# Interface.net
KiCad netlist of a schematic drawn in Altium Designer
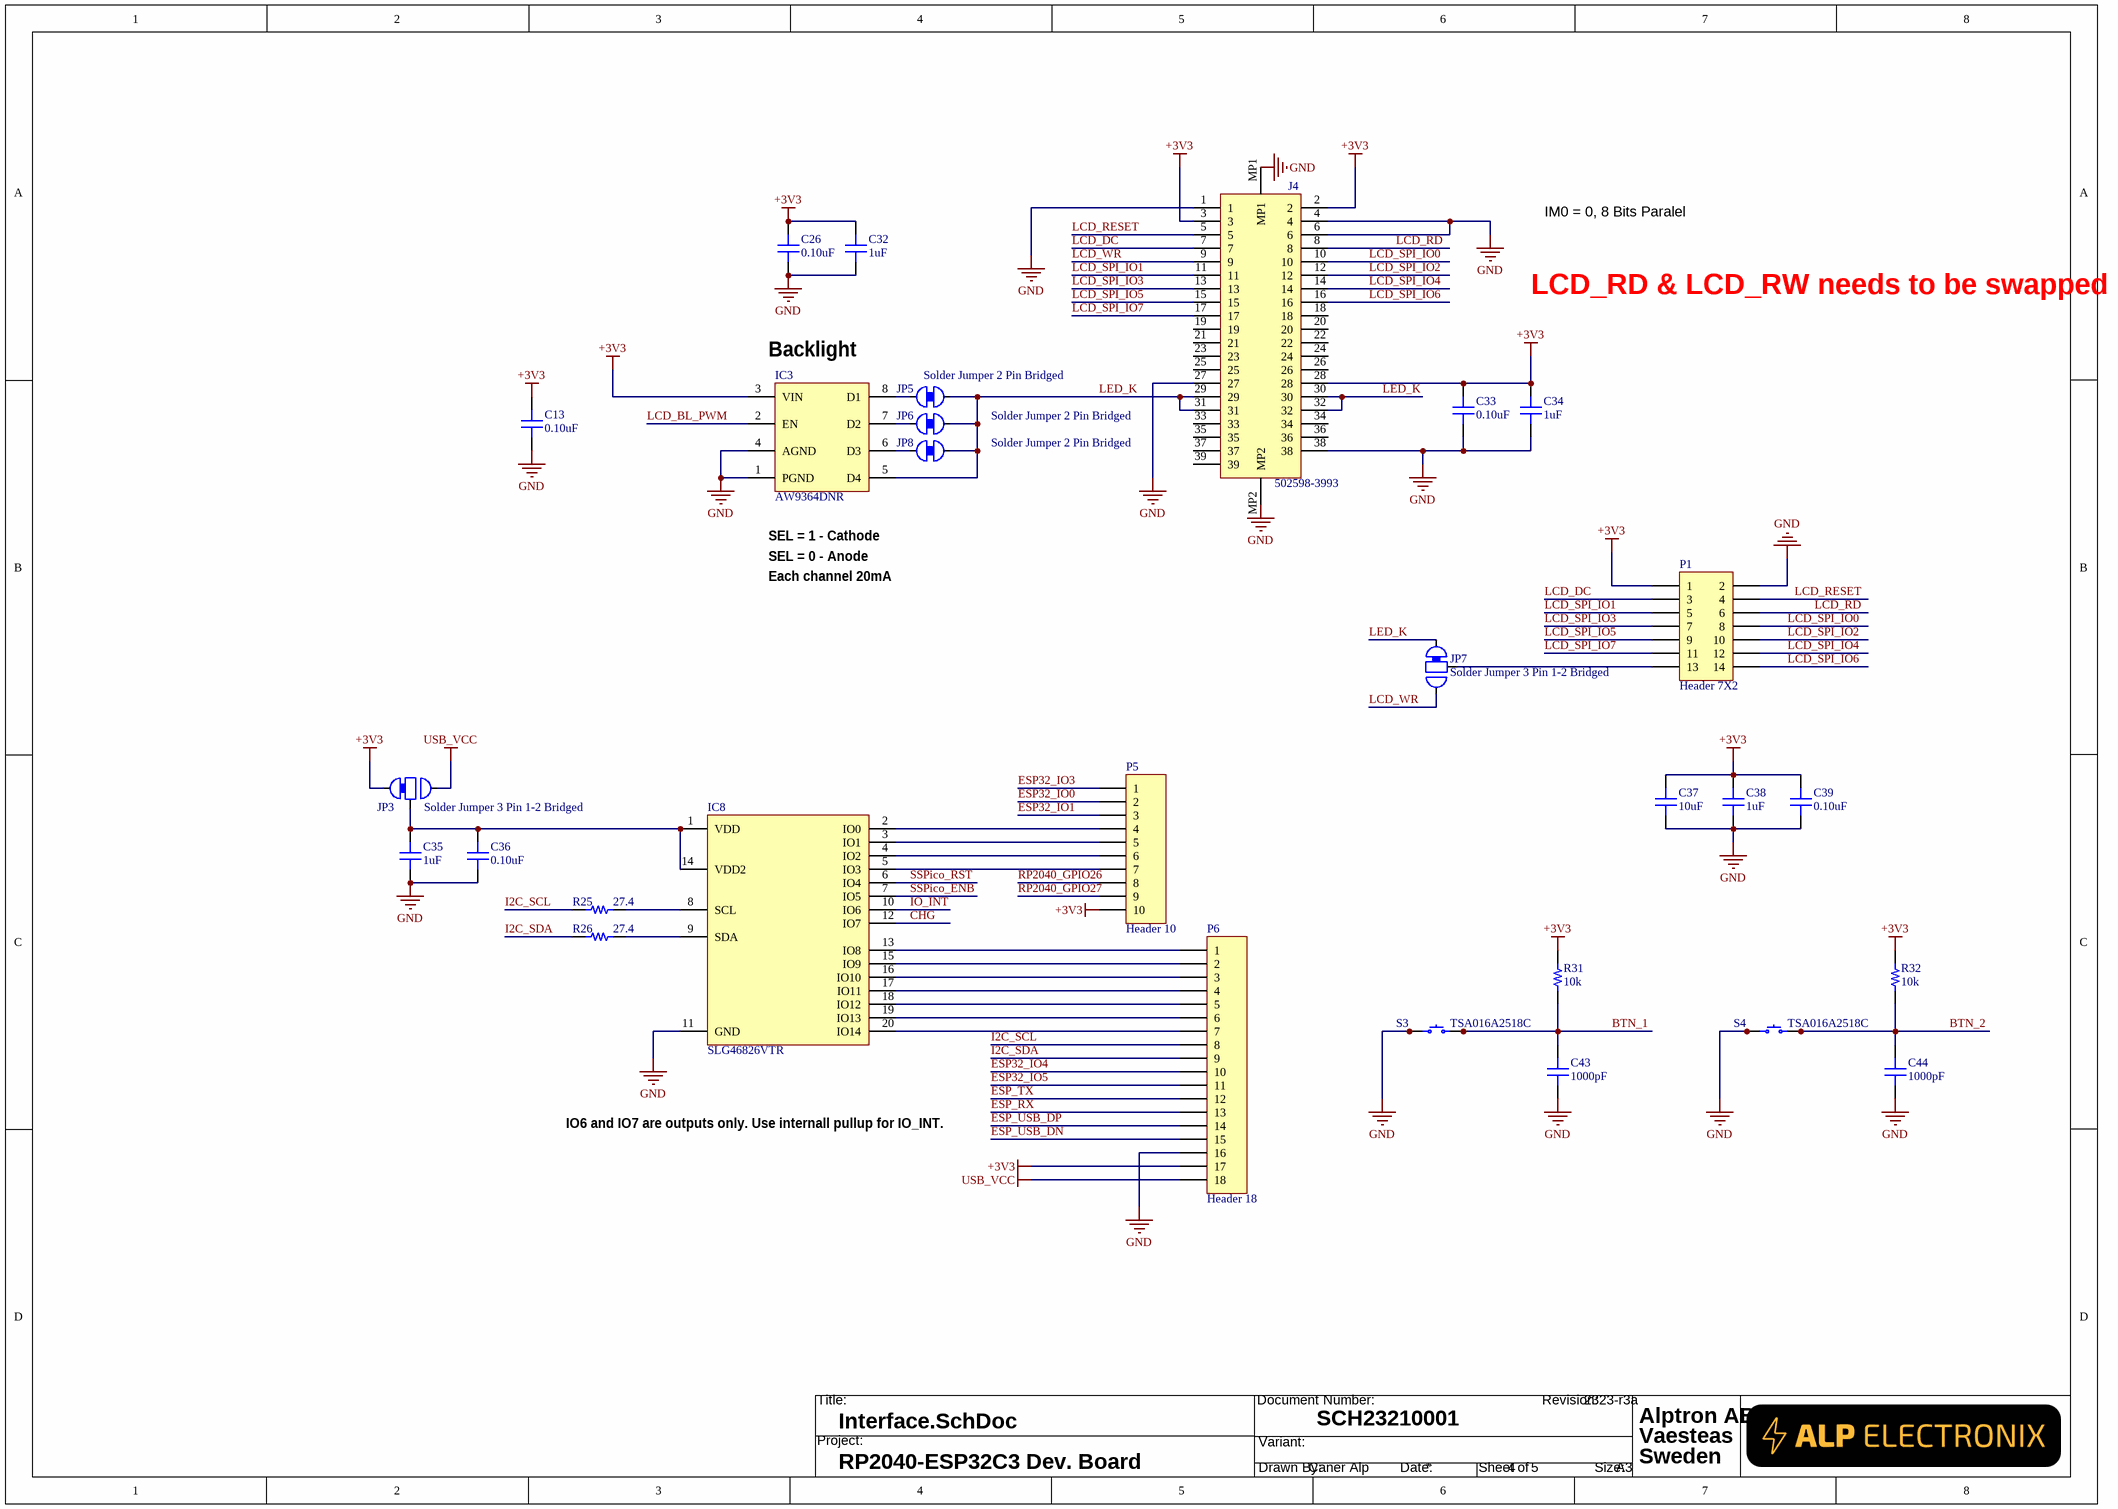
[diagram p0: Interface.SchDoc]

(export (version "E")
  (design (tool "Eeschema 10.0.6"))
  (components
    (comp (ref "C13")
      (value "0.10uF")
      (footprint "CAP 0402/1005")
      (description "CAP CER 0.1UF 10V X5R 0402")
      (fields (field (name "PART NUMBER") "LMK105BJ104KV-F") (field (name "MANUFACTURER") "Taiyo Yuden"))
      (libsource (lib "Celestial Library Database") (part "Capacitor"))
    )
    (comp (ref "C26")
      (value "0.10uF")
      (footprint "CAP 0402/1005")
      (description "CAP CER 0.1UF 10V X5R 0402")
      (fields (field (name "PART NUMBER") "LMK105BJ104KV-F") (field (name "MANUFACTURER") "Taiyo Yuden"))
      (libsource (lib "Celestial Library Database") (part "Capacitor"))
    )
    (comp (ref "C32")
      (value "1uF")
      (footprint "CAP 0402/1005")
      (description "CAP CER 1UF 6.3V X7R 0402")
      (fields
        (field (name "PART NUMBER") "GRM155R70J105KA12D")
        (field (name "MANUFACTURER") "Murata Electronics North America")
      )
      (libsource (lib "Celestial Library Database") (part "Capacitor"))
    )
    (comp (ref "C33")
      (value "0.10uF")
      (footprint "CAP 0402/1005")
      (description "CAP CER 0.1UF 10V X5R 0402")
      (fields (field (name "PART NUMBER") "LMK105BJ104KV-F") (field (name "MANUFACTURER") "Taiyo Yuden"))
      (libsource (lib "Celestial Library Database") (part "Capacitor"))
    )
    (comp (ref "C34")
      (value "1uF")
      (footprint "CAP 0402/1005")
      (description "CAP CER 1UF 6.3V X7R 0402")
      (fields
        (field (name "PART NUMBER") "GRM155R70J105KA12D")
        (field (name "MANUFACTURER") "Murata Electronics North America")
      )
      (libsource (lib "Celestial Library Database") (part "Capacitor"))
    )
    (comp (ref "C35")
      (value "1uF")
      (footprint "CAP 0402/1005")
      (description "CAP CER 1UF 6.3V X7R 0402")
      (fields
        (field (name "PART NUMBER") "GRM155R70J105KA12D")
        (field (name "MANUFACTURER") "Murata Electronics North America")
      )
      (libsource (lib "Celestial Library Database") (part "Capacitor"))
    )
    (comp (ref "C36")
      (value "0.10uF")
      (footprint "CAP 0402/1005")
      (description "CAP CER 0.1UF 10V X5R 0402")
      (fields (field (name "PART NUMBER") "LMK105BJ104KV-F") (field (name "MANUFACTURER") "Taiyo Yuden"))
      (libsource (lib "Celestial Library Database") (part "Capacitor"))
    )
    (comp (ref "C37")
      (value "10uF")
      (footprint "CAP 0603/1608")
      (description "CAP CER 10UF 6.3V X5R 0603")
      (fields
        (field (name "PART NUMBER") "GRM188R60J106ME47D")
        (field (name "MANUFACTURER") "Murata Electronics North America")
      )
      (libsource (lib "Celestial Library Database") (part "Capacitor"))
    )
    (comp (ref "C38")
      (value "1uF")
      (footprint "CAP 0402/1005")
      (description "CAP CER 1UF 6.3V X7R 0402")
      (fields
        (field (name "PART NUMBER") "GRM155R70J105KA12D")
        (field (name "MANUFACTURER") "Murata Electronics North America")
      )
      (libsource (lib "Celestial Library Database") (part "Capacitor"))
    )
    (comp (ref "C39")
      (value "0.10uF")
      (footprint "CAP 0402/1005")
      (description "CAP CER 0.1UF 10V X5R 0402")
      (fields (field (name "PART NUMBER") "LMK105BJ104KV-F") (field (name "MANUFACTURER") "Taiyo Yuden"))
      (libsource (lib "Celestial Library Database") (part "Capacitor"))
    )
    (comp (ref "C43")
      (value "1000pF")
      (footprint "CAP 0402/1005")
      (description "CAP CER 1000PF 50V C0G 0402")
      (fields
        (field (name "PART NUMBER") "C1005C0G1H102J050BA")
        (field (name "MANUFACTURER") "TDK Corporation")
      )
      (libsource (lib "Celestial Library Database") (part "Capacitor"))
    )
    (comp (ref "C44")
      (value "1000pF")
      (footprint "CAP 0402/1005")
      (description "CAP CER 1000PF 50V C0G 0402")
      (fields
        (field (name "PART NUMBER") "C1005C0G1H102J050BA")
        (field (name "MANUFACTURER") "TDK Corporation")
      )
      (libsource (lib "Celestial Library Database") (part "Capacitor"))
    )
    (comp (ref "IC3")
      (value "AW9364DNR")
      (footprint "RP2040_ESP32-C3 Dev Board PCB Lib:MAXIM TDFN-8 2x2MM")
      (description "-40℃~+85℃ DFN-8(2x2) LED Drivers ROHS")
      (libsource (lib "RP2040_ESP32-C3 Dev Board SCH Lib") (part "AW9364DNR"))
    )
    (comp (ref "IC8")
      (value "SLG46826VTR")
      (footprint "RP2040_ESP32-C3 Dev Board PCB Lib:SLG46826VTR")
      (fields
        (field (name "MOUSER PART NUMBER") "724-SLG46826VTR")
        (field (name "MANUFACTURER") "Renesas")
        (field (name "MANUFACTURER PART NUMBER") "SLG46826V")
      )
      (libsource (lib "RP2040_ESP32-C3 Dev Board SCH Lib") (part "SLG46826VTR"))
    )
    (comp (ref "J4")
      (value "502598-3993")
      (footprint "RP2040_ESP32-C3 Dev Board PCB Lib:5025983993")
      (description "Connector")
      (fields (field (name "MOUSER PART NUMBER") "538-502598-3993"))
      (libsource (lib "RP2040_ESP32-C3 Dev Board SCH Lib") (part "502598-3993"))
    )
    (comp (ref "JP3")
      (value "Solder Jumper 3 Pin 1-2 Bridged")
      (footprint "Jumper:SolderJumper-3_P1.3mm_Bridged12_RoundedPad1.0x1.5mm")
      (libsource (lib "Jumper") (part "SolderJumper_3_Bridged12"))
    )
    (comp (ref "JP5")
      (value "Solder Jumper 2 Pin Bridged")
      (footprint "Jumper:SolderJumper-2_P1.3mm_Bridged_RoundedPad1.0x1.5mm")
      (libsource (lib "Jumper") (part "SolderJumper_2_Bridged"))
    )
    (comp (ref "JP6")
      (value "Solder Jumper 2 Pin Bridged")
      (footprint "Jumper:SolderJumper-2_P1.3mm_Bridged_RoundedPad1.0x1.5mm")
      (libsource (lib "Jumper") (part "SolderJumper_2_Bridged"))
    )
    (comp (ref "JP7")
      (value "Solder Jumper 3 Pin 1-2 Bridged")
      (footprint "Jumper:SolderJumper-3_P1.3mm_Bridged12_RoundedPad1.0x1.5mm")
      (libsource (lib "") (part "SolderJumper_3_Bridged12_1"))
    )
    (comp (ref "JP8")
      (value "Solder Jumper 2 Pin Bridged")
      (footprint "Jumper:SolderJumper-2_P1.3mm_Bridged_RoundedPad1.0x1.5mm")
      (libsource (lib "Jumper") (part "SolderJumper_2_Bridged"))
    )
    (comp (ref "P1")
      (value "Header 7X2")
      (footprint "HDR2X7")
      (description "Header, 7-Pin, Dual row")
      (fields (field (name "PUBLISHER") "Altium Limited"))
      (libsource (lib "Miscellaneous Connectors") (part "Header 7X2"))
    )
    (comp (ref "P5")
      (value "Header 10")
      (footprint "3D FootPrint_Backup:Female Header 2.54mm - 10 Pin")
      (description "Header, 10-Pin")
      (fields (field (name "PUBLISHER") "Altium Limited"))
      (libsource (lib "Miscellaneous Connectors") (part "Header 10"))
    )
    (comp (ref "P6")
      (value "Header 18")
      (footprint "3D FootPrint_Backup:Female Header 2.54mm - 18 Pin")
      (description "Header, 18-Pin")
      (fields (field (name "PUBLISHER") "Altium Limited"))
      (libsource (lib "Miscellaneous Connectors") (part "Header 18"))
    )
    (comp (ref "R25")
      (value "27.4")
      (footprint "RES 0402/1005")
      (description "RES SMD 27.4 OHM 1% 1/10W 0402")
      (fields
        (field (name "PART NUMBER") "ERJ-2RKF27R4X")
        (field (name "MANUFACTURER") "Panasonic Electronic Components")
      )
      (libsource (lib "Celestial Library Database") (part "Resistor"))
    )
    (comp (ref "R26")
      (value "27.4")
      (footprint "RES 0402/1005")
      (description "RES SMD 27.4 OHM 1% 1/10W 0402")
      (fields
        (field (name "PART NUMBER") "ERJ-2RKF27R4X")
        (field (name "MANUFACTURER") "Panasonic Electronic Components")
      )
      (libsource (lib "Celestial Library Database") (part "Resistor"))
    )
    (comp (ref "R31")
      (value "10k")
      (footprint "RES 0402/1005")
      (description "RES SMD 10K OHM 5% 1/16W 0402")
      (fields (field (name "PART NUMBER") "RC0402JR-0710KL") (field (name "MANUFACTURER") "Yageo"))
      (libsource (lib "Celestial Library Database") (part "Resistor"))
    )
    (comp (ref "R32")
      (value "10k")
      (footprint "RES 0402/1005")
      (description "RES SMD 10K OHM 5% 1/16W 0402")
      (fields (field (name "PART NUMBER") "RC0402JR-0710KL") (field (name "MANUFACTURER") "Yageo"))
      (libsource (lib "Celestial Library Database") (part "Resistor"))
    )
    (comp (ref "S3")
      (value "TSA016A2518C")
      (footprint "RP2040_ESP32-C3 Dev Board PCB Lib:TSA016A2518C")
      (description "SWITCH TACTILE SPST-NO 0.05A 16V")
      (fields (field (name "MANUFACTURER") "C&K"))
      (libsource (lib "Celestial Altium Library - altium_library") (part "SPST-NO 4 PIN"))
    )
    (comp (ref "S4")
      (value "TSA016A2518C")
      (footprint "RP2040_ESP32-C3 Dev Board PCB Lib:TSA016A2518C")
      (description "SWITCH TACTILE SPST-NO 0.05A 16V")
      (fields (field (name "MANUFACTURER") "C&K"))
      (libsource (lib "Celestial Altium Library - altium_library") (part "SPST-NO 4 PIN"))
    )
  )
  (nets
    (net (code "1") (name "+3V3") (class "Default")
      (node (ref "C13") (pin "2") (pinfunction "2_2") (pintype "passive"))
      (node (ref "C26") (pin "2") (pinfunction "2_2") (pintype "passive"))
      (node (ref "C32") (pin "2") (pinfunction "2_2") (pintype "passive"))
      (node (ref "C33") (pin "2") (pinfunction "2_2") (pintype "passive"))
      (node (ref "C34") (pin "2") (pinfunction "2_2") (pintype "passive"))
      (node (ref "C37") (pin "2") (pinfunction "2_2") (pintype "passive"))
      (node (ref "C38") (pin "2") (pinfunction "2_2") (pintype "passive"))
      (node (ref "C39") (pin "2") (pinfunction "2_2") (pintype "passive"))
      (node (ref "IC3") (pin "3") (pinfunction "VIN_3") (pintype "passive"))
      (node (ref "J4") (pin "2") (pinfunction "2_2") (pintype "passive"))
      (node (ref "J4") (pin "28") (pinfunction "28_28") (pintype "passive"))
      (node (ref "J4") (pin "3") (pinfunction "3_3") (pintype "passive"))
      (node (ref "JP3") (pin "1") (pinfunction "A_1") (pintype "passive"))
      (node (ref "P1") (pin "1") (pinfunction "1_1") (pintype "passive"))
      (node (ref "P5") (pin "10") (pinfunction "10_10") (pintype "passive"))
      (node (ref "P6") (pin "17") (pinfunction "17_17") (pintype "passive"))
      (node (ref "R31") (pin "2") (pinfunction "2_2") (pintype "passive"))
      (node (ref "R32") (pin "2") (pinfunction "2_2") (pintype "passive"))
    )
    (net (code "2") (name "/BTN_1") (class "Default")
      (node (ref "C43") (pin "2") (pinfunction "2_2") (pintype "passive"))
      (node (ref "R31") (pin "1") (pinfunction "1_1") (pintype "passive"))
      (node (ref "S3") (pin "3") (pinfunction "3_3") (pintype "passive"))
      (node (ref "S3") (pin "4") (pinfunction "4_4") (pintype "passive"))
    )
    (net (code "3") (name "/BTN_2") (class "Default")
      (node (ref "C44") (pin "2") (pinfunction "2_2") (pintype "passive"))
      (node (ref "R32") (pin "1") (pinfunction "1_1") (pintype "passive"))
      (node (ref "S4") (pin "3") (pinfunction "3_3") (pintype "passive"))
      (node (ref "S4") (pin "4") (pinfunction "4_4") (pintype "passive"))
    )
    (net (code "4") (name "/CHG") (class "Default")
      (node (ref "IC8") (pin "12") (pinfunction "IO7_12") (pintype "passive"))
    )
    (net (code "5") (name "/ESP32_IO0") (class "Default")
      (node (ref "P5") (pin "2") (pinfunction "2_2") (pintype "passive"))
    )
    (net (code "6") (name "/ESP32_IO1") (class "Default")
      (node (ref "P5") (pin "3") (pinfunction "3_3") (pintype "passive"))
    )
    (net (code "7") (name "/ESP32_IO3") (class "Default")
      (node (ref "P5") (pin "1") (pinfunction "1_1") (pintype "passive"))
    )
    (net (code "8") (name "/ESP32_IO4") (class "Default")
      (node (ref "P6") (pin "10") (pinfunction "10_10") (pintype "passive"))
    )
    (net (code "9") (name "/ESP32_IO5") (class "Default")
      (node (ref "P6") (pin "11") (pinfunction "11_11") (pintype "passive"))
    )
    (net (code "10") (name "/ESP_RX") (class "Default")
      (node (ref "P6") (pin "13") (pinfunction "13_13") (pintype "passive"))
    )
    (net (code "11") (name "/ESP_TX") (class "Default")
      (node (ref "P6") (pin "12") (pinfunction "12_12") (pintype "passive"))
    )
    (net (code "12") (name "/ESP_USB_DN") (class "Default")
      (node (ref "P6") (pin "15") (pinfunction "15_15") (pintype "passive"))
    )
    (net (code "13") (name "/ESP_USB_DP") (class "Default")
      (node (ref "P6") (pin "14") (pinfunction "14_14") (pintype "passive"))
    )
    (net (code "14") (name "/I2C_SCL") (class "Default")
      (node (ref "P6") (pin "8") (pinfunction "8_8") (pintype "passive"))
      (node (ref "R25") (pin "1") (pinfunction "1_1") (pintype "passive"))
    )
    (net (code "15") (name "/I2C_SDA") (class "Default")
      (node (ref "P6") (pin "9") (pinfunction "9_9") (pintype "passive"))
      (node (ref "R26") (pin "1") (pinfunction "1_1") (pintype "passive"))
    )
    (net (code "16") (name "/IO_INT") (class "Default")
      (node (ref "IC8") (pin "10") (pinfunction "IO6_10") (pintype "passive"))
    )
    (net (code "17") (name "/LCD_BL_PWM") (class "Default")
      (node (ref "IC3") (pin "2") (pinfunction "EN_2") (pintype "passive"))
    )
    (net (code "18") (name "/LCD_DC") (class "Default")
      (node (ref "J4") (pin "7") (pinfunction "7_7") (pintype "passive"))
      (node (ref "P1") (pin "3") (pinfunction "3_3") (pintype "passive"))
    )
    (net (code "19") (name "/LCD_RD") (class "Default")
      (node (ref "J4") (pin "8") (pinfunction "8_8") (pintype "passive"))
      (node (ref "P1") (pin "6") (pinfunction "6_6") (pintype "passive"))
    )
    (net (code "20") (name "/LCD_RESET") (class "Default")
      (node (ref "J4") (pin "5") (pinfunction "5_5") (pintype "passive"))
      (node (ref "P1") (pin "4") (pinfunction "4_4") (pintype "passive"))
    )
    (net (code "21") (name "/LCD_SPI_IO0") (class "Default")
      (node (ref "J4") (pin "10") (pinfunction "10_10") (pintype "passive"))
      (node (ref "P1") (pin "8") (pinfunction "8_8") (pintype "passive"))
    )
    (net (code "22") (name "/LCD_SPI_IO1") (class "Default")
      (node (ref "J4") (pin "11") (pinfunction "11_11") (pintype "passive"))
      (node (ref "P1") (pin "5") (pinfunction "5_5") (pintype "passive"))
    )
    (net (code "23") (name "/LCD_SPI_IO2") (class "Default")
      (node (ref "J4") (pin "12") (pinfunction "12_12") (pintype "passive"))
      (node (ref "P1") (pin "10") (pinfunction "10_10") (pintype "passive"))
    )
    (net (code "24") (name "/LCD_SPI_IO3") (class "Default")
      (node (ref "J4") (pin "13") (pinfunction "13_13") (pintype "passive"))
      (node (ref "P1") (pin "7") (pinfunction "7_7") (pintype "passive"))
    )
    (net (code "25") (name "/LCD_SPI_IO4") (class "Default")
      (node (ref "J4") (pin "14") (pinfunction "14_14") (pintype "passive"))
      (node (ref "P1") (pin "12") (pinfunction "12_12") (pintype "passive"))
    )
    (net (code "26") (name "/LCD_SPI_IO5") (class "Default")
      (node (ref "J4") (pin "15") (pinfunction "15_15") (pintype "passive"))
      (node (ref "P1") (pin "9") (pinfunction "9_9") (pintype "passive"))
    )
    (net (code "27") (name "/LCD_SPI_IO6") (class "Default")
      (node (ref "J4") (pin "16") (pinfunction "16_16") (pintype "passive"))
      (node (ref "P1") (pin "14") (pinfunction "14_14") (pintype "passive"))
    )
    (net (code "28") (name "/LCD_SPI_IO7") (class "Default")
      (node (ref "J4") (pin "17") (pinfunction "17_17") (pintype "passive"))
      (node (ref "P1") (pin "11") (pinfunction "11_11") (pintype "passive"))
    )
    (net (code "29") (name "/LCD_WR") (class "Default")
      (node (ref "J4") (pin "9") (pinfunction "9_9") (pintype "passive"))
      (node (ref "JP7") (pin "3") (pinfunction "B_3") (pintype "passive"))
    )
    (net (code "30") (name "/LED_K") (class "Default")
      (node (ref "IC3") (pin "5") (pinfunction "D4_5") (pintype "passive"))
      (node (ref "J4") (pin "29") (pinfunction "29_29") (pintype "passive"))
      (node (ref "J4") (pin "30") (pinfunction "30_30") (pintype "passive"))
      (node (ref "J4") (pin "31") (pinfunction "31_31") (pintype "passive"))
      (node (ref "J4") (pin "32") (pinfunction "32_32") (pintype "passive"))
      (node (ref "JP5") (pin "2") (pinfunction "B_2") (pintype "passive"))
      (node (ref "JP6") (pin "2") (pinfunction "B_2") (pintype "passive"))
      (node (ref "JP7") (pin "1") (pinfunction "A_1") (pintype "passive"))
      (node (ref "JP8") (pin "2") (pinfunction "B_2") (pintype "passive"))
    )
    (net (code "31") (name "/RP2040_GPIO26") (class "Default")
      (node (ref "P5") (pin "8") (pinfunction "8_8") (pintype "passive"))
    )
    (net (code "32") (name "/RP2040_GPIO27") (class "Default")
      (node (ref "P5") (pin "9") (pinfunction "9_9") (pintype "passive"))
    )
    (net (code "33") (name "/SSPico_ENB") (class "Default")
      (node (ref "IC8") (pin "7") (pinfunction "IO5_7") (pintype "passive"))
    )
    (net (code "34") (name "/SSPico_RST") (class "Default")
      (node (ref "IC8") (pin "6") (pinfunction "IO4_6") (pintype "passive"))
    )
    (net (code "35") (name "GND") (class "Default")
      (node (ref "C13") (pin "1") (pinfunction "1_1") (pintype "passive"))
      (node (ref "C26") (pin "1") (pinfunction "1_1") (pintype "passive"))
      (node (ref "C32") (pin "1") (pinfunction "1_1") (pintype "passive"))
      (node (ref "C33") (pin "1") (pinfunction "1_1") (pintype "passive"))
      (node (ref "C34") (pin "1") (pinfunction "1_1") (pintype "passive"))
      (node (ref "C35") (pin "1") (pinfunction "1_1") (pintype "passive"))
      (node (ref "C36") (pin "1") (pinfunction "1_1") (pintype "passive"))
      (node (ref "C37") (pin "1") (pinfunction "1_1") (pintype "passive"))
      (node (ref "C38") (pin "1") (pinfunction "1_1") (pintype "passive"))
      (node (ref "C39") (pin "1") (pinfunction "1_1") (pintype "passive"))
      (node (ref "C43") (pin "1") (pinfunction "1_1") (pintype "passive"))
      (node (ref "C44") (pin "1") (pinfunction "1_1") (pintype "passive"))
      (node (ref "IC3") (pin "1") (pinfunction "PGND_1") (pintype "passive"))
      (node (ref "IC3") (pin "4") (pinfunction "AGND_4") (pintype "passive"))
      (node (ref "IC8") (pin "11") (pinfunction "GND_11") (pintype "passive"))
      (node (ref "J4") (pin "1") (pinfunction "1_1") (pintype "passive"))
      (node (ref "J4") (pin "27") (pinfunction "27_27") (pintype "passive"))
      (node (ref "J4") (pin "38") (pinfunction "38_38") (pintype "passive"))
      (node (ref "J4") (pin "4") (pinfunction "4_4") (pintype "passive"))
      (node (ref "J4") (pin "6") (pinfunction "6_6") (pintype "passive"))
      (node (ref "J4") (pin "MP1") (pinfunction "MP1_MP1") (pintype "passive"))
      (node (ref "J4") (pin "MP2") (pinfunction "MP2_MP2") (pintype "passive"))
      (node (ref "P1") (pin "2") (pinfunction "2_2") (pintype "passive"))
      (node (ref "P6") (pin "16") (pinfunction "16_16") (pintype "passive"))
      (node (ref "S3") (pin "1") (pinfunction "1_1") (pintype "passive"))
      (node (ref "S3") (pin "2") (pinfunction "2_2") (pintype "passive"))
      (node (ref "S4") (pin "1") (pinfunction "1_1") (pintype "passive"))
      (node (ref "S4") (pin "2") (pinfunction "2_2") (pintype "passive"))
    )
    (net (code "36") (name "Net-(IC3-D1)") (class "Default")
      (node (ref "IC3") (pin "8") (pinfunction "D1_8") (pintype "passive"))
      (node (ref "JP5") (pin "1") (pinfunction "A_1") (pintype "passive"))
    )
    (net (code "37") (name "Net-(IC3-D2)") (class "Default")
      (node (ref "IC3") (pin "7") (pinfunction "D2_7") (pintype "passive"))
      (node (ref "JP6") (pin "1") (pinfunction "A_1") (pintype "passive"))
    )
    (net (code "38") (name "Net-(IC3-D3)") (class "Default")
      (node (ref "IC3") (pin "6") (pinfunction "D3_6") (pintype "passive"))
      (node (ref "JP8") (pin "1") (pinfunction "A_1") (pintype "passive"))
    )
    (net (code "39") (name "Net-(IC8-IO0)") (class "Default")
      (node (ref "IC8") (pin "2") (pinfunction "IO0_2") (pintype "passive"))
      (node (ref "P5") (pin "4") (pinfunction "4_4") (pintype "passive"))
    )
    (net (code "40") (name "Net-(IC8-IO1)") (class "Default")
      (node (ref "IC8") (pin "3") (pinfunction "IO1_3") (pintype "passive"))
      (node (ref "P5") (pin "5") (pinfunction "5_5") (pintype "passive"))
    )
    (net (code "41") (name "Net-(IC8-IO2)") (class "Default")
      (node (ref "IC8") (pin "4") (pinfunction "IO2_4") (pintype "passive"))
      (node (ref "P5") (pin "6") (pinfunction "6_6") (pintype "passive"))
    )
    (net (code "42") (name "Net-(IC8-IO3)") (class "Default")
      (node (ref "IC8") (pin "5") (pinfunction "IO3_5") (pintype "passive"))
      (node (ref "P5") (pin "7") (pinfunction "7_7") (pintype "passive"))
    )
    (net (code "43") (name "Net-(IC8-IO8)") (class "Default")
      (node (ref "IC8") (pin "13") (pinfunction "IO8_13") (pintype "passive"))
      (node (ref "P6") (pin "1") (pinfunction "1_1") (pintype "passive"))
    )
    (net (code "44") (name "Net-(IC8-IO9)") (class "Default")
      (node (ref "IC8") (pin "15") (pinfunction "IO9_15") (pintype "passive"))
      (node (ref "P6") (pin "2") (pinfunction "2_2") (pintype "passive"))
    )
    (net (code "45") (name "Net-(IC8-IO10)") (class "Default")
      (node (ref "IC8") (pin "16") (pinfunction "IO10_16") (pintype "passive"))
      (node (ref "P6") (pin "3") (pinfunction "3_3") (pintype "passive"))
    )
    (net (code "46") (name "Net-(IC8-IO11)") (class "Default")
      (node (ref "IC8") (pin "17") (pinfunction "IO11_17") (pintype "passive"))
      (node (ref "P6") (pin "4") (pinfunction "4_4") (pintype "passive"))
    )
    (net (code "47") (name "Net-(IC8-IO12)") (class "Default")
      (node (ref "IC8") (pin "18") (pinfunction "IO12_18") (pintype "passive"))
      (node (ref "P6") (pin "5") (pinfunction "5_5") (pintype "passive"))
    )
    (net (code "48") (name "Net-(IC8-IO13)") (class "Default")
      (node (ref "IC8") (pin "19") (pinfunction "IO13_19") (pintype "passive"))
      (node (ref "P6") (pin "6") (pinfunction "6_6") (pintype "passive"))
    )
    (net (code "49") (name "Net-(IC8-IO14)") (class "Default")
      (node (ref "IC8") (pin "20") (pinfunction "IO14_20") (pintype "passive"))
      (node (ref "P6") (pin "7") (pinfunction "7_7") (pintype "passive"))
    )
    (net (code "50") (name "Net-(IC8-SCL)") (class "Default")
      (node (ref "IC8") (pin "8") (pinfunction "SCL_8") (pintype "passive"))
      (node (ref "R25") (pin "2") (pinfunction "2_2") (pintype "passive"))
    )
    (net (code "51") (name "Net-(IC8-SDA)") (class "Default")
      (node (ref "IC8") (pin "9") (pinfunction "SDA_9") (pintype "passive"))
      (node (ref "R26") (pin "2") (pinfunction "2_2") (pintype "passive"))
    )
    (net (code "52") (name "Net-(IC8-VDD)") (class "Default")
      (node (ref "C35") (pin "2") (pinfunction "2_2") (pintype "passive"))
      (node (ref "C36") (pin "2") (pinfunction "2_2") (pintype "passive"))
      (node (ref "IC8") (pin "1") (pinfunction "VDD_1") (pintype "passive"))
      (node (ref "IC8") (pin "14") (pinfunction "VDD2_14") (pintype "passive"))
      (node (ref "JP3") (pin "2") (pinfunction "C_2") (pintype "passive"))
    )
    (net (code "53") (name "Net-(JP7-C)") (class "Default")
      (node (ref "JP7") (pin "2") (pinfunction "C_2") (pintype "passive"))
      (node (ref "P1") (pin "13") (pinfunction "13_13") (pintype "passive"))
    )
    (net (code "54") (name "USB_VCC") (class "Default")
      (node (ref "JP3") (pin "3") (pinfunction "B_3") (pintype "passive"))
      (node (ref "P6") (pin "18") (pinfunction "18_18") (pintype "passive"))
    )
    (net (code "55") (name "unconnected-(J4-Pad18)") (class "Default")
      (node (ref "J4") (pin "18") (pinfunction "18_18") (pintype "passive"))
    )
    (net (code "56") (name "unconnected-(J4-Pad19)") (class "Default")
      (node (ref "J4") (pin "19") (pinfunction "19_19") (pintype "passive"))
    )
    (net (code "57") (name "unconnected-(J4-Pad20)") (class "Default")
      (node (ref "J4") (pin "20") (pinfunction "20_20") (pintype "passive"))
    )
    (net (code "58") (name "unconnected-(J4-Pad21)") (class "Default")
      (node (ref "J4") (pin "21") (pinfunction "21_21") (pintype "passive"))
    )
    (net (code "59") (name "unconnected-(J4-Pad22)") (class "Default")
      (node (ref "J4") (pin "22") (pinfunction "22_22") (pintype "passive"))
    )
    (net (code "60") (name "unconnected-(J4-Pad23)") (class "Default")
      (node (ref "J4") (pin "23") (pinfunction "23_23") (pintype "passive"))
    )
    (net (code "61") (name "unconnected-(J4-Pad24)") (class "Default")
      (node (ref "J4") (pin "24") (pinfunction "24_24") (pintype "passive"))
    )
    (net (code "62") (name "unconnected-(J4-Pad25)") (class "Default")
      (node (ref "J4") (pin "25") (pinfunction "25_25") (pintype "passive"))
    )
    (net (code "63") (name "unconnected-(J4-Pad26)") (class "Default")
      (node (ref "J4") (pin "26") (pinfunction "26_26") (pintype "passive"))
    )
    (net (code "64") (name "unconnected-(J4-Pad33)") (class "Default")
      (node (ref "J4") (pin "33") (pinfunction "33_33") (pintype "passive"))
    )
    (net (code "65") (name "unconnected-(J4-Pad34)") (class "Default")
      (node (ref "J4") (pin "34") (pinfunction "34_34") (pintype "passive"))
    )
    (net (code "66") (name "unconnected-(J4-Pad35)") (class "Default")
      (node (ref "J4") (pin "35") (pinfunction "35_35") (pintype "passive"))
    )
    (net (code "67") (name "unconnected-(J4-Pad36)") (class "Default")
      (node (ref "J4") (pin "36") (pinfunction "36_36") (pintype "passive"))
    )
    (net (code "68") (name "unconnected-(J4-Pad37)") (class "Default")
      (node (ref "J4") (pin "37") (pinfunction "37_37") (pintype "passive"))
    )
    (net (code "69") (name "unconnected-(J4-Pad39)") (class "Default")
      (node (ref "J4") (pin "39") (pinfunction "39_39") (pintype "passive"))
    )
  )
)
